# EDW-project-final.net
KiCad netlist of a schematic drawn in EAGLE
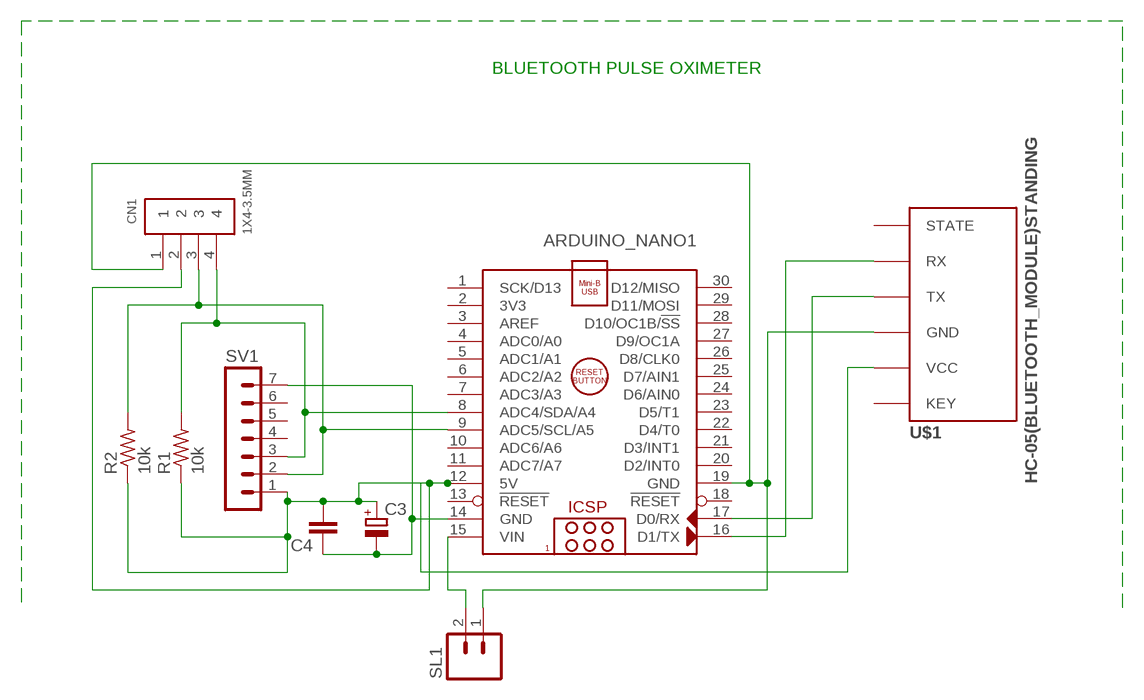
[diagram p0: schematic, sheet 1]

(export (version "E")
  (design (tool "Eeschema 10.0.6"))
  (components
    (comp (ref "ARDUINO_NANO1")
      (value "ARDUINO_NANO")
      (footprint "eagle-import:ARDUINO_NANO")
      (libsource (lib "eagle-import") (part "ARDUINO_NANO"))
    )
    (comp (ref "C3")
      (value "CPOL-EUE2.5-6")
      (footprint "eagle-import:E2,5-6")
      (libsource (lib "eagle-import") (part "CPOL-EUE2.5-6"))
    )
    (comp (ref "C4")
      (value "C-EU025-024X044")
      (footprint "eagle-import:C025-024X044")
      (libsource (lib "eagle-import") (part "C-EU025-024X044"))
    )
    (comp (ref "CN1")
      (value "1X4-3.5MM")
      (footprint "eagle-import:1X04-3.5MM")
      (libsource (lib "eagle-import") (part "1X4-3.5MM"))
    )
    (comp (ref "R1")
      (value "10k")
      (footprint "eagle-import:0207_7")
      (libsource (lib "eagle-import") (part "RESISTOR0207/7"))
    )
    (comp (ref "R2")
      (value "10k")
      (footprint "eagle-import:0207_7")
      (libsource (lib "eagle-import") (part "RESISTOR0207/7"))
    )
    (comp (ref "SL1")
      (value "M02")
      (footprint "eagle-import:02P")
      (libsource (lib "eagle-import") (part "M02"))
    )
    (comp (ref "SV1")
      (value "MA07-1")
      (footprint "eagle-import:MA07-1")
      (libsource (lib "eagle-import") (part "MA07-1"))
    )
    (comp (ref "U$1")
      (value "HC-05(BLUETOOTH_MODULE)STANDING")
      (footprint "eagle-import:HC-05(STANDING)")
      (libsource (lib "eagle-import") (part "HC-05(BLUETOOTH_MODULE)STANDING"))
    )
  )
  (nets
    (net (code "1") (name "Net-(ARDUINO_NANO1-5V)") (class "Default")
      (node (ref "ARDUINO_NANO1") (pin "12") (pinfunction "5V_12") (pintype "power_in"))
      (node (ref "C3") (pin "+") (pinfunction "+_+") (pintype "passive"))
      (node (ref "C4") (pin "2") (pinfunction "2_2") (pintype "passive"))
      (node (ref "CN1") (pin "2") (pinfunction "2_2") (pintype "bidirectional"))
      (node (ref "R1") (pin "1") (pinfunction "1_1") (pintype "passive"))
      (node (ref "R2") (pin "1") (pinfunction "1_1") (pintype "passive"))
      (node (ref "SV1") (pin "1") (pinfunction "1_1") (pintype "passive"))
      (node (ref "U$1") (pin "VCC") (pinfunction "VCC_VCC") (pintype "power_in"))
    )
    (net (code "2") (name "Net-(ARDUINO_NANO1-ADC4{slash}SDA{slash}A4)") (class "Default")
      (node (ref "ARDUINO_NANO1") (pin "8") (pinfunction "ADC4/SDA/A4_8") (pintype "bidirectional"))
      (node (ref "CN1") (pin "4") (pinfunction "4_4") (pintype "bidirectional"))
      (node (ref "R1") (pin "2") (pinfunction "2_2") (pintype "passive"))
      (node (ref "SV1") (pin "3") (pinfunction "3_3") (pintype "passive"))
    )
    (net (code "3") (name "Net-(ARDUINO_NANO1-ADC5{slash}SCL{slash}A5)") (class "Default")
      (node (ref "ARDUINO_NANO1") (pin "9") (pinfunction "ADC5/SCL/A5_9") (pintype "bidirectional"))
      (node (ref "CN1") (pin "3") (pinfunction "3_3") (pintype "bidirectional"))
      (node (ref "R2") (pin "2") (pinfunction "2_2") (pintype "passive"))
      (node (ref "SV1") (pin "2") (pinfunction "2_2") (pintype "passive"))
    )
    (net (code "4") (name "Net-(ARDUINO_NANO1-D0{slash}RX)") (class "Default")
      (node (ref "ARDUINO_NANO1") (pin "17") (pinfunction "D0/RX_17") (pintype "bidirectional"))
      (node (ref "U$1") (pin "TX") (pinfunction "TX_TX") (pintype "bidirectional"))
    )
    (net (code "5") (name "Net-(ARDUINO_NANO1-D1{slash}TX)") (class "Default")
      (node (ref "ARDUINO_NANO1") (pin "16") (pinfunction "D1/TX_16") (pintype "bidirectional"))
      (node (ref "U$1") (pin "RX") (pinfunction "RX_RX") (pintype "bidirectional"))
    )
    (net (code "6") (name "Net-(ARDUINO_NANO1-GND-Pad14)") (class "Default")
      (node (ref "ARDUINO_NANO1") (pin "14") (pinfunction "GND_14") (pintype "power_in"))
      (node (ref "C3") (pin "-") (pinfunction "-_-") (pintype "passive"))
      (node (ref "C4") (pin "1") (pinfunction "1_1") (pintype "passive"))
      (node (ref "SV1") (pin "7") (pinfunction "7_7") (pintype "passive"))
    )
    (net (code "7") (name "Net-(ARDUINO_NANO1-GND-Pad19)") (class "Default")
      (node (ref "ARDUINO_NANO1") (pin "19") (pinfunction "GND_19") (pintype "power_in"))
      (node (ref "CN1") (pin "1") (pinfunction "1_1") (pintype "bidirectional"))
      (node (ref "SL1") (pin "1") (pinfunction "1_1") (pintype "passive"))
      (node (ref "U$1") (pin "GND") (pinfunction "GND_GND") (pintype "power_in"))
    )
    (net (code "8") (name "Net-(ARDUINO_NANO1-VIN)") (class "Default")
      (node (ref "ARDUINO_NANO1") (pin "15") (pinfunction "VIN_15") (pintype "power_in"))
      (node (ref "SL1") (pin "2") (pinfunction "2_2") (pintype "passive"))
    )
    (net (code "9") (name "unconnected-(ARDUINO_NANO1-3V3-Pad2)") (class "Default")
      (node (ref "ARDUINO_NANO1") (pin "2") (pinfunction "3V3_2") (pintype "output"))
    )
    (net (code "10") (name "unconnected-(ARDUINO_NANO1-ADC0{slash}A0-Pad4)") (class "Default")
      (node (ref "ARDUINO_NANO1") (pin "4") (pinfunction "ADC0/A0_4") (pintype "bidirectional"))
    )
    (net (code "11") (name "unconnected-(ARDUINO_NANO1-ADC1{slash}A1-Pad5)") (class "Default")
      (node (ref "ARDUINO_NANO1") (pin "5") (pinfunction "ADC1/A1_5") (pintype "bidirectional"))
    )
    (net (code "12") (name "unconnected-(ARDUINO_NANO1-ADC2{slash}A2-Pad6)") (class "Default")
      (node (ref "ARDUINO_NANO1") (pin "6") (pinfunction "ADC2/A2_6") (pintype "bidirectional"))
    )
    (net (code "13") (name "unconnected-(ARDUINO_NANO1-ADC3{slash}A3-Pad7)") (class "Default")
      (node (ref "ARDUINO_NANO1") (pin "7") (pinfunction "ADC3/A3_7") (pintype "bidirectional"))
    )
    (net (code "14") (name "unconnected-(ARDUINO_NANO1-ADC6{slash}A6-Pad10)") (class "Default")
      (node (ref "ARDUINO_NANO1") (pin "10") (pinfunction "ADC6/A6_10") (pintype "bidirectional"))
    )
    (net (code "15") (name "unconnected-(ARDUINO_NANO1-ADC7{slash}A7-Pad11)") (class "Default")
      (node (ref "ARDUINO_NANO1") (pin "11") (pinfunction "ADC7/A7_11") (pintype "bidirectional"))
    )
    (net (code "16") (name "unconnected-(ARDUINO_NANO1-AREF-Pad3)") (class "Default")
      (node (ref "ARDUINO_NANO1") (pin "3") (pinfunction "AREF_3") (pintype "input"))
    )
    (net (code "17") (name "unconnected-(ARDUINO_NANO1-D2{slash}INT0-Pad20)") (class "Default")
      (node (ref "ARDUINO_NANO1") (pin "20") (pinfunction "D2/INT0_20") (pintype "bidirectional"))
    )
    (net (code "18") (name "unconnected-(ARDUINO_NANO1-D3{slash}INT1-Pad21)") (class "Default")
      (node (ref "ARDUINO_NANO1") (pin "21") (pinfunction "D3/INT1_21") (pintype "bidirectional"))
    )
    (net (code "19") (name "unconnected-(ARDUINO_NANO1-D4{slash}T0-Pad22)") (class "Default")
      (node (ref "ARDUINO_NANO1") (pin "22") (pinfunction "D4/T0_22") (pintype "bidirectional"))
    )
    (net (code "20") (name "unconnected-(ARDUINO_NANO1-D5{slash}T1-Pad23)") (class "Default")
      (node (ref "ARDUINO_NANO1") (pin "23") (pinfunction "D5/T1_23") (pintype "bidirectional"))
    )
    (net (code "21") (name "unconnected-(ARDUINO_NANO1-D6{slash}AIN0-Pad24)") (class "Default")
      (node (ref "ARDUINO_NANO1") (pin "24") (pinfunction "D6/AIN0_24") (pintype "bidirectional"))
    )
    (net (code "22") (name "unconnected-(ARDUINO_NANO1-D7{slash}AIN1-Pad25)") (class "Default")
      (node (ref "ARDUINO_NANO1") (pin "25") (pinfunction "D7/AIN1_25") (pintype "bidirectional"))
    )
    (net (code "23") (name "unconnected-(ARDUINO_NANO1-D8{slash}CLK0-Pad26)") (class "Default")
      (node (ref "ARDUINO_NANO1") (pin "26") (pinfunction "D8/CLK0_26") (pintype "bidirectional"))
    )
    (net (code "24") (name "unconnected-(ARDUINO_NANO1-D9{slash}OC1A-Pad27)") (class "Default")
      (node (ref "ARDUINO_NANO1") (pin "27") (pinfunction "D9/OC1A_27") (pintype "bidirectional"))
    )
    (net (code "25") (name "unconnected-(ARDUINO_NANO1-D10{slash}OC1B{slash}~{SS}-Pad28)") (class "Default")
      (node (ref "ARDUINO_NANO1") (pin "28") (pinfunction "D10/OC1B/~{SS}_28") (pintype "bidirectional"))
    )
    (net (code "26") (name "unconnected-(ARDUINO_NANO1-D11{slash}MOSI-Pad29)") (class "Default")
      (node (ref "ARDUINO_NANO1") (pin "29") (pinfunction "D11/MOSI_29") (pintype "bidirectional"))
    )
    (net (code "27") (name "unconnected-(ARDUINO_NANO1-D12{slash}MISO-Pad30)") (class "Default")
      (node (ref "ARDUINO_NANO1") (pin "30") (pinfunction "D12/MISO_30") (pintype "bidirectional"))
    )
    (net (code "28") (name "unconnected-(ARDUINO_NANO1-SCK{slash}D13-Pad1)") (class "Default")
      (node (ref "ARDUINO_NANO1") (pin "1") (pinfunction "SCK/D13_1") (pintype "bidirectional"))
    )
    (net (code "29") (name "unconnected-(ARDUINO_NANO1-~{RESET}-Pad13)") (class "Default")
      (node (ref "ARDUINO_NANO1") (pin "13") (pinfunction "~{RESET}_13") (pintype "input"))
    )
    (net (code "30") (name "unconnected-(ARDUINO_NANO1-~{RESET}-Pad18)") (class "Default")
      (node (ref "ARDUINO_NANO1") (pin "18") (pinfunction "~{RESET}_18") (pintype "input"))
    )
    (net (code "31") (name "unconnected-(SV1-Pad4)") (class "Default")
      (node (ref "SV1") (pin "4") (pinfunction "4_4") (pintype "passive"))
    )
    (net (code "32") (name "unconnected-(SV1-Pad5)") (class "Default")
      (node (ref "SV1") (pin "5") (pinfunction "5_5") (pintype "passive"))
    )
    (net (code "33") (name "unconnected-(SV1-Pad6)") (class "Default")
      (node (ref "SV1") (pin "6") (pinfunction "6_6") (pintype "passive"))
    )
    (net (code "34") (name "unconnected-(U$1-PadKEY)") (class "Default")
      (node (ref "U$1") (pin "KEY") (pinfunction "KEY_KEY") (pintype "bidirectional"))
    )
    (net (code "35") (name "unconnected-(U$1-PadSTATE)") (class "Default")
      (node (ref "U$1") (pin "STATE") (pinfunction "STATE_STATE") (pintype "bidirectional"))
    )
  )
)
